# CHIP_ziffy_v5.net
KiCad netlist of a schematic drawn in EAGLE
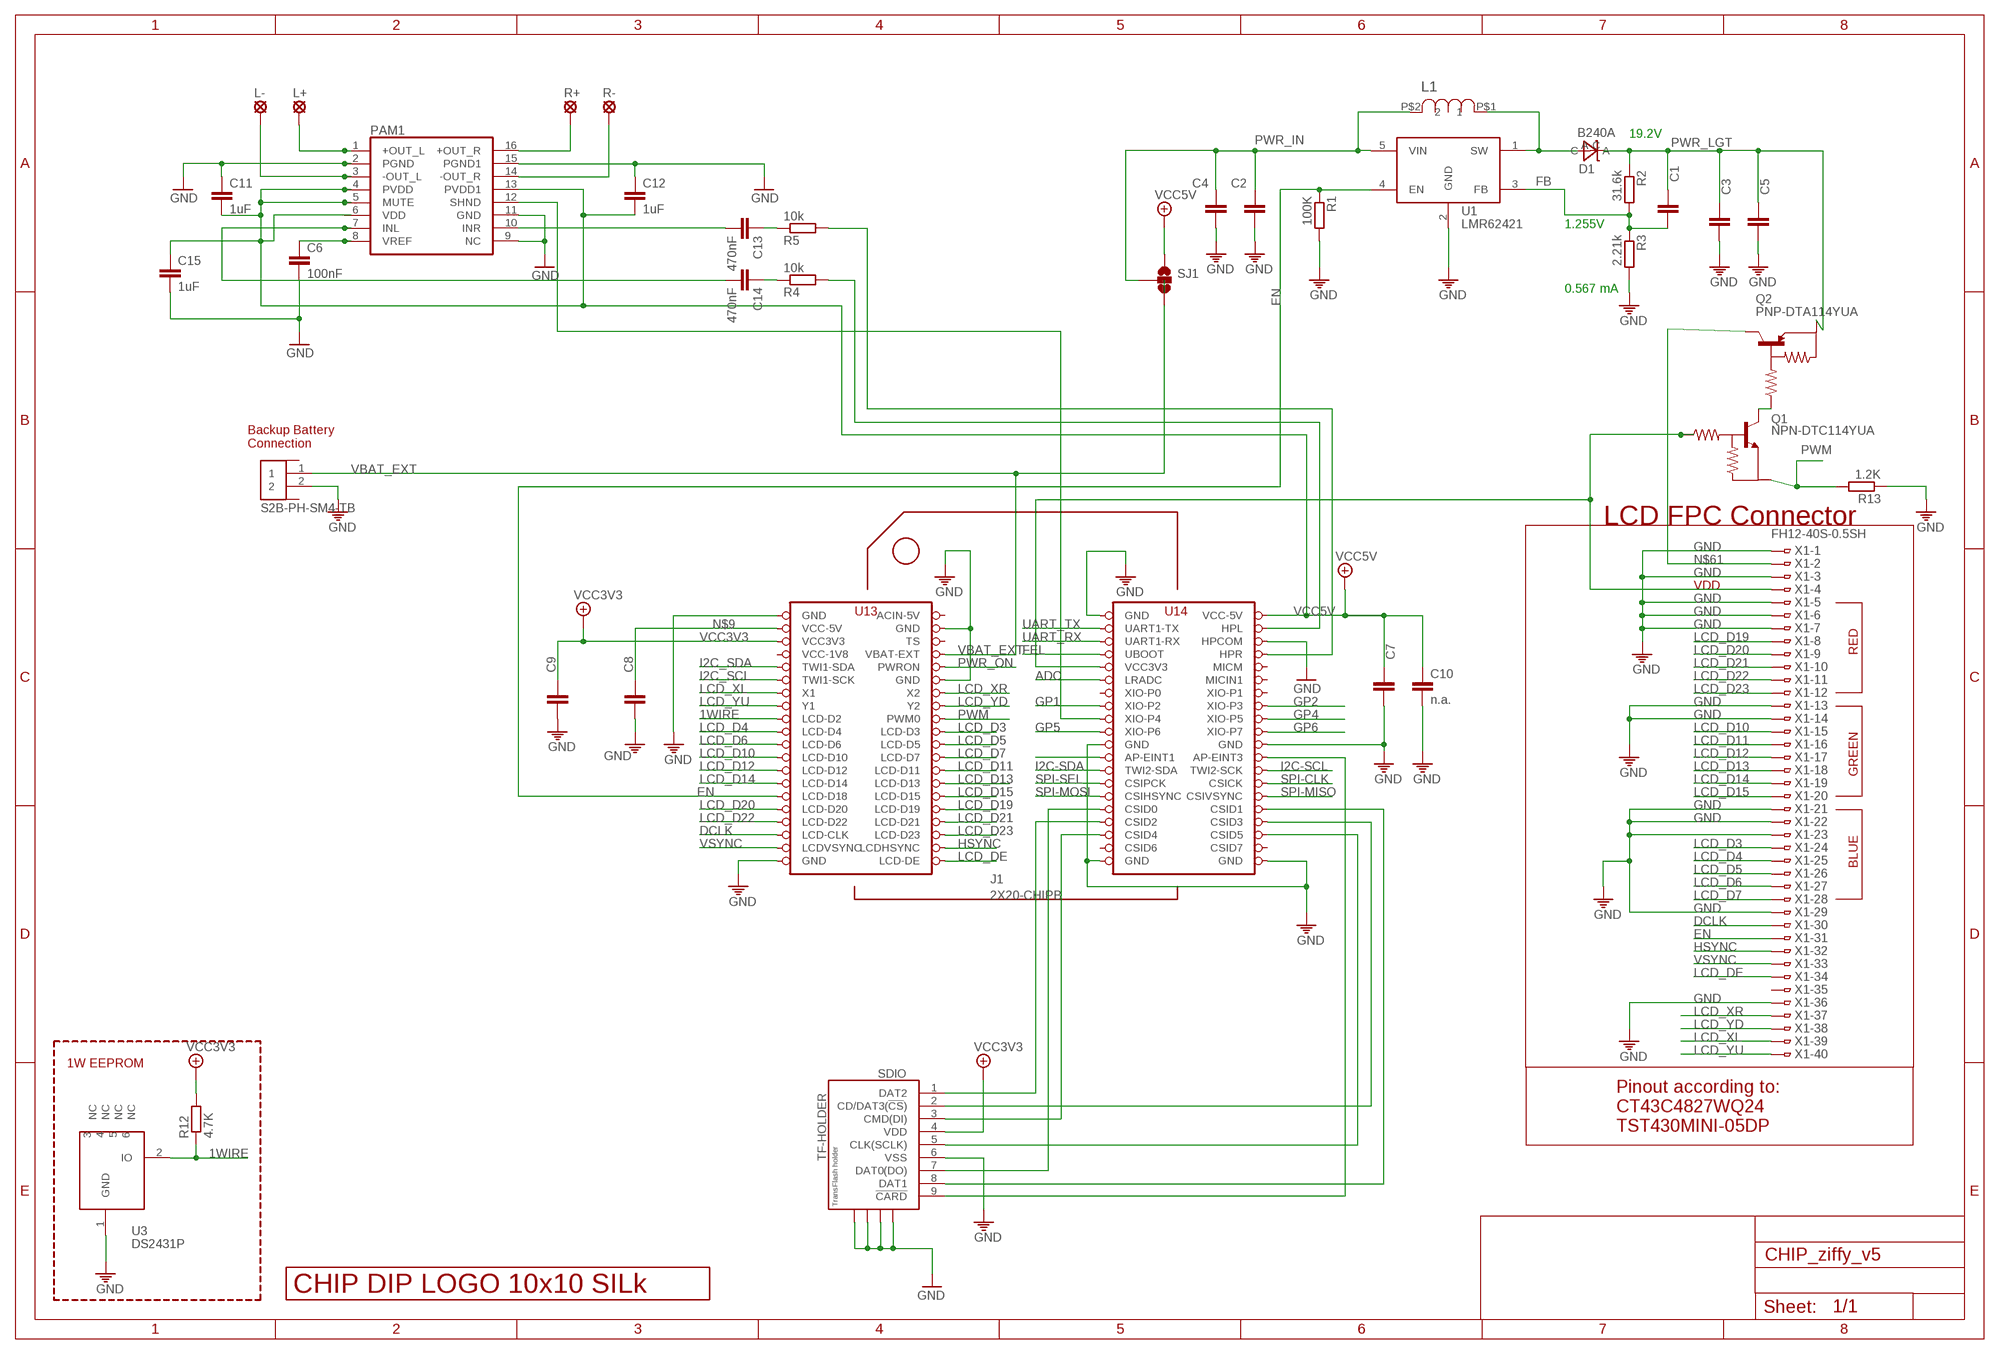
[diagram p0: schematic, sheet 1]

(export (version "E")
  (design (tool "Eeschema 10.0.6"))
  (components
    (comp (ref "C1")
      (value "220pF")
      (footprint "eagle-import:C0805")
      (libsource (lib "eagle-import") (part "C-EUC0805"))
    )
    (comp (ref "C2")
      (value "100nF")
      (footprint "eagle-import:C0805")
      (libsource (lib "eagle-import") (part "C-EUC0805"))
    )
    (comp (ref "C3")
      (value "100nF")
      (footprint "eagle-import:C0805")
      (libsource (lib "eagle-import") (part "C-EUC0805"))
    )
    (comp (ref "C4")
      (value "22uF")
      (footprint "eagle-import:C0805")
      (libsource (lib "eagle-import") (part "C-EUC0805"))
    )
    (comp (ref "C5")
      (value "22uF")
      (footprint "eagle-import:C0805")
      (libsource (lib "eagle-import") (part "C-EUC0805"))
    )
    (comp (ref "C6")
      (value "100nF")
      (footprint "eagle-import:C0805")
      (libsource (lib "eagle-import") (part "C-EUC0805"))
    )
    (comp (ref "C7")
      (value "n.a.")
      (footprint "eagle-import:C0805")
      (libsource (lib "eagle-import") (part "C-EUC0805"))
    )
    (comp (ref "C8")
      (value "100nF")
      (footprint "eagle-import:C0805")
      (libsource (lib "eagle-import") (part "C-EUC0805"))
    )
    (comp (ref "C9")
      (value "100nF")
      (footprint "eagle-import:C0805")
      (libsource (lib "eagle-import") (part "C-EUC0805"))
    )
    (comp (ref "C10")
      (value "n.a.")
      (footprint "eagle-import:C0805")
      (libsource (lib "eagle-import") (part "C-EUC0805"))
    )
    (comp (ref "C11")
      (value "1uF")
      (footprint "eagle-import:C0805")
      (libsource (lib "eagle-import") (part "C-EUC0805"))
    )
    (comp (ref "C12")
      (value "1uF")
      (footprint "eagle-import:C0805")
      (libsource (lib "eagle-import") (part "C-EUC0805"))
    )
    (comp (ref "C13")
      (value "470nF")
      (footprint "eagle-import:C0805")
      (libsource (lib "eagle-import") (part "C-EUC0805"))
    )
    (comp (ref "C14")
      (value "470nF")
      (footprint "eagle-import:C0805")
      (libsource (lib "eagle-import") (part "C-EUC0805"))
    )
    (comp (ref "C15")
      (value "1uF")
      (footprint "eagle-import:C0805")
      (libsource (lib "eagle-import") (part "C-EUC0805"))
    )
    (comp (ref "D1")
      (value "B240A")
      (footprint "eagle-import:DO-214AC")
      (fields (field (name "MFG") "DIGIKEY") (field (name "VENDOR_PART_NUMBER") "B240A-13-F"))
      (libsource (lib "eagle-import") (part "DIODE_SCHTKY_B240"))
    )
    (comp (ref "J1")
      (value "2X20-CHIPB")
      (footprint "eagle-import:2X20CHIP_SM")
      (libsource (lib "eagle-import") (part "2X20-CHIPB"))
    )
    (comp (ref "J3")
      (value "S2B-PH-SM4-TB")
      (footprint "eagle-import:S2B-PH-SM4-TB")
      (fields (field (name "MFG") "DIGIKEY") (field (name "VENDOR_PART_NUMBER") "S2B-PH-SM4-TB(LF)(SN)"))
      (libsource (lib "eagle-import") (part "S2B-PH-SM4-TB"))
    )
    (comp (ref "L+")
      (value "SE11")
      (footprint "eagle-import:SE11")
      (libsource (lib "eagle-import") (part "SE11"))
    )
    (comp (ref "L-")
      (value "SE11")
      (footprint "eagle-import:SE11")
      (libsource (lib "eagle-import") (part "SE11"))
    )
    (comp (ref "L1")
      (value "SRN6045-100M")
      (footprint "eagle-import:SRN6045")
      (fields (field (name "MFG") "DIGIKEY"))
      (libsource (lib "eagle-import") (part "SRN6045-100M"))
    )
    (comp (ref "PAM1")
      (value "PAM8403")
      (footprint "eagle-import:SOP-16")
      (libsource (lib "eagle-import") (part "PAM8403"))
    )
    (comp (ref "Q1")
      (value "NPN-DTC114YUA")
      (footprint "eagle-import:SOT323")
      (libsource (lib "eagle-import") (part "NPN-DTC114YUA"))
    )
    (comp (ref "Q2")
      (value "PNP-DTA114YUA")
      (footprint "eagle-import:SOT323")
      (libsource (lib "eagle-import") (part "PNP-DTA114YUA"))
    )
    (comp (ref "R+")
      (value "SE11")
      (footprint "eagle-import:SE11")
      (libsource (lib "eagle-import") (part "SE11"))
    )
    (comp (ref "R-")
      (value "SE11")
      (footprint "eagle-import:SE11")
      (libsource (lib "eagle-import") (part "SE11"))
    )
    (comp (ref "R1")
      (value "100K")
      (footprint "eagle-import:M0805")
      (libsource (lib "eagle-import") (part "R-EU_M0805"))
    )
    (comp (ref "R2")
      (value "31.6k")
      (footprint "eagle-import:M0805")
      (libsource (lib "eagle-import") (part "R-EU_M0805"))
    )
    (comp (ref "R3")
      (value "2.21k")
      (footprint "eagle-import:M0805")
      (libsource (lib "eagle-import") (part "R-EU_M0805"))
    )
    (comp (ref "R4")
      (value "10k")
      (footprint "eagle-import:R0805")
      (libsource (lib "eagle-import") (part "R-EU_R0805"))
    )
    (comp (ref "R5")
      (value "10k")
      (footprint "eagle-import:R0805")
      (libsource (lib "eagle-import") (part "R-EU_R0805"))
    )
    (comp (ref "R12")
      (value "4.7K")
      (footprint "eagle-import:M0805")
      (libsource (lib "eagle-import") (part "R-EU_M0805"))
    )
    (comp (ref "R13")
      (value "1.2K")
      (footprint "eagle-import:M0805")
      (libsource (lib "eagle-import") (part "R-EU_M0805"))
    )
    (comp (ref "SDIO")
      (value "TF-HOLDER")
      (footprint "eagle-import:TF-PULL")
      (libsource (lib "eagle-import") (part "TF-HOLDER"))
    )
    (comp (ref "SJ1")
      (value "SOLDERJUMPER_2WAYT")
      (footprint "eagle-import:SJ_2")
      (libsource (lib "eagle-import") (part "SOLDERJUMPER_2WAYT"))
    )
    (comp (ref "U$2")
      (value "LOGO_10X10_SILK")
      (footprint "eagle-import:LOGO2_10X10_SILK")
      (libsource (lib "eagle-import") (part "LOGO_10X10_SILK"))
    )
    (comp (ref "U1")
      (value "LMR62421")
      (footprint "eagle-import:SOT23-5")
      (fields (field (name "MFG") "DIGIKEY") (field (name "VENDOR_PART_NUMBER") "LMR62421XMFE/NOPB"))
      (libsource (lib "eagle-import") (part "LMR62421"))
    )
    (comp (ref "U3")
      (value "DS2431P")
      (footprint "eagle-import:TSOC6")
      (fields (field (name "MFG") "DIGIKEY") (field (name "VENDOR_PART_NUMBER") "DS2431P+T&R"))
      (libsource (lib "eagle-import") (part "DS2431P"))
    )
    (comp (ref "X1")
      (value "FH12-40S-0.5SH")
      (footprint "eagle-import:FH12-40S-0.5SH")
      (fields (field (name "MFG") "DIGIKEY") (field (name "VENDOR_PART_NUMBER") "FH12-40S-0.5SH(55)"))
      (libsource (lib "eagle-import") (part "FH12-40S-0.5SH"))
    )
  )
  (nets
    (net (code "1") (name "/1WIRE") (class "Default")
      (node (ref "J1") (pin "LCD-D2") (pinfunction "LCD-D2_LCD-D2") (pintype "passive"))
      (node (ref "R12") (pin "1") (pinfunction "1_1") (pintype "passive"))
      (node (ref "U3") (pin "2") (pinfunction "IO_2") (pintype "bidirectional"))
    )
    (net (code "2") (name "/ADC") (class "Default")
      (node (ref "J1") (pin "LRADC") (pinfunction "LRADC_LRADC") (pintype "passive"))
    )
    (net (code "3") (name "/DCLK") (class "Default")
      (node (ref "J1") (pin "LCD-CLK") (pinfunction "LCD-CLK_LCD-CLK") (pintype "passive"))
      (node (ref "X1") (pin "30") (pinfunction "1_30") (pintype "passive"))
    )
    (net (code "4") (name "/EN") (class "Default")
      (node (ref "J1") (pin "LCD-D18") (pinfunction "LCD-D18_LCD-D18") (pintype "passive"))
      (node (ref "R1") (pin "1") (pinfunction "1_1") (pintype "passive"))
      (node (ref "U1") (pin "4") (pinfunction "EN_4") (pintype "bidirectional"))
      (node (ref "X1") (pin "31") (pinfunction "1_31") (pintype "passive"))
    )
    (net (code "5") (name "/FB") (class "Default")
      (node (ref "C1") (pin "2") (pinfunction "2_2") (pintype "passive"))
      (node (ref "R2") (pin "2") (pinfunction "2_2") (pintype "passive"))
      (node (ref "R3") (pin "1") (pinfunction "1_1") (pintype "passive"))
      (node (ref "U1") (pin "3") (pinfunction "FB_3") (pintype "bidirectional"))
    )
    (net (code "6") (name "/FEL") (class "Default")
      (node (ref "J1") (pin "FEL") (pinfunction "UBOOT_FEL") (pintype "passive"))
    )
    (net (code "7") (name "/GP1") (class "Default")
      (node (ref "J1") (pin "XIO-P2") (pinfunction "XIO-P2_XIO-P2") (pintype "passive"))
    )
    (net (code "8") (name "/GP2") (class "Default")
      (node (ref "J1") (pin "XIO-P3") (pinfunction "XIO-P3_XIO-P3") (pintype "passive"))
    )
    (net (code "9") (name "/GP4") (class "Default")
      (node (ref "J1") (pin "XIO-P5") (pinfunction "XIO-P5_XIO-P5") (pintype "passive"))
    )
    (net (code "10") (name "/GP5") (class "Default")
      (node (ref "J1") (pin "XIO-P6") (pinfunction "XIO-P6_XIO-P6") (pintype "passive"))
    )
    (net (code "11") (name "/GP6") (class "Default")
      (node (ref "J1") (pin "XIO-P7") (pinfunction "XIO-P7_XIO-P7") (pintype "passive"))
    )
    (net (code "12") (name "/HSYNC") (class "Default")
      (node (ref "J1") (pin "LCD-HSYNC") (pinfunction "LCDHSYNC_LCD-HSYNC") (pintype "passive"))
      (node (ref "X1") (pin "32") (pinfunction "1_32") (pintype "passive"))
    )
    (net (code "13") (name "/I2C-SCL") (class "Default")
      (node (ref "J1") (pin "TWI2-SCK") (pinfunction "TWI2-SCK_TWI2-SCK") (pintype "passive"))
    )
    (net (code "14") (name "/I2C-SDA") (class "Default")
      (node (ref "J1") (pin "TWI2-SDA") (pinfunction "TWI2-SDA_TWI2-SDA") (pintype "passive"))
    )
    (net (code "15") (name "/I2C_SCL") (class "Default")
      (node (ref "J1") (pin "TWI1-SCK") (pinfunction "TWI1-SCK_TWI1-SCK") (pintype "passive"))
    )
    (net (code "16") (name "/I2C_SDA") (class "Default")
      (node (ref "J1") (pin "TWI1-SDA") (pinfunction "TWI1-SDA_TWI1-SDA") (pintype "passive"))
    )
    (net (code "17") (name "/LCD_D3") (class "Default")
      (node (ref "J1") (pin "LCD-D3") (pinfunction "LCD-D3_LCD-D3") (pintype "passive"))
      (node (ref "X1") (pin "24") (pinfunction "1_24") (pintype "passive"))
    )
    (net (code "18") (name "/LCD_D4") (class "Default")
      (node (ref "J1") (pin "LCD-D4") (pinfunction "LCD-D4_LCD-D4") (pintype "passive"))
      (node (ref "X1") (pin "25") (pinfunction "1_25") (pintype "passive"))
    )
    (net (code "19") (name "/LCD_D5") (class "Default")
      (node (ref "J1") (pin "LCD-D5") (pinfunction "LCD-D5_LCD-D5") (pintype "passive"))
      (node (ref "X1") (pin "26") (pinfunction "1_26") (pintype "passive"))
    )
    (net (code "20") (name "/LCD_D6") (class "Default")
      (node (ref "J1") (pin "LCD-D6") (pinfunction "LCD-D6_LCD-D6") (pintype "passive"))
      (node (ref "X1") (pin "27") (pinfunction "1_27") (pintype "passive"))
    )
    (net (code "21") (name "/LCD_D7") (class "Default")
      (node (ref "J1") (pin "LCD-D7") (pinfunction "LCD-D7_LCD-D7") (pintype "passive"))
      (node (ref "X1") (pin "28") (pinfunction "1_28") (pintype "passive"))
    )
    (net (code "22") (name "/LCD_D10") (class "Default")
      (node (ref "J1") (pin "LCD-D10") (pinfunction "LCD-D10_LCD-D10") (pintype "passive"))
      (node (ref "X1") (pin "15") (pinfunction "1_15") (pintype "passive"))
    )
    (net (code "23") (name "/LCD_D11") (class "Default")
      (node (ref "J1") (pin "LCD-D11") (pinfunction "LCD-D11_LCD-D11") (pintype "passive"))
      (node (ref "X1") (pin "16") (pinfunction "1_16") (pintype "passive"))
    )
    (net (code "24") (name "/LCD_D12") (class "Default")
      (node (ref "J1") (pin "LCD-D12") (pinfunction "LCD-D12_LCD-D12") (pintype "passive"))
      (node (ref "X1") (pin "17") (pinfunction "1_17") (pintype "passive"))
    )
    (net (code "25") (name "/LCD_D13") (class "Default")
      (node (ref "J1") (pin "LCD-D13") (pinfunction "LCD-D13_LCD-D13") (pintype "passive"))
      (node (ref "X1") (pin "18") (pinfunction "1_18") (pintype "passive"))
    )
    (net (code "26") (name "/LCD_D14") (class "Default")
      (node (ref "J1") (pin "LCD-D14") (pinfunction "LCD-D14_LCD-D14") (pintype "passive"))
      (node (ref "X1") (pin "19") (pinfunction "1_19") (pintype "passive"))
    )
    (net (code "27") (name "/LCD_D15") (class "Default")
      (node (ref "J1") (pin "LCD-D15") (pinfunction "LCD-D15_LCD-D15") (pintype "passive"))
      (node (ref "X1") (pin "20") (pinfunction "1_20") (pintype "passive"))
    )
    (net (code "28") (name "/LCD_D19") (class "Default")
      (node (ref "J1") (pin "LCD-D19") (pinfunction "LCD-D19_LCD-D19") (pintype "passive"))
      (node (ref "X1") (pin "8") (pinfunction "1_8") (pintype "passive"))
    )
    (net (code "29") (name "/LCD_D20") (class "Default")
      (node (ref "J1") (pin "LCD-D20") (pinfunction "LCD-D20_LCD-D20") (pintype "passive"))
      (node (ref "X1") (pin "9") (pinfunction "1_9") (pintype "passive"))
    )
    (net (code "30") (name "/LCD_D21") (class "Default")
      (node (ref "J1") (pin "LCD-D21") (pinfunction "LCD-D21_LCD-D21") (pintype "passive"))
      (node (ref "X1") (pin "10") (pinfunction "1_10") (pintype "passive"))
    )
    (net (code "31") (name "/LCD_D22") (class "Default")
      (node (ref "J1") (pin "LCD-D22") (pinfunction "LCD-D22_LCD-D22") (pintype "passive"))
      (node (ref "X1") (pin "11") (pinfunction "1_11") (pintype "passive"))
    )
    (net (code "32") (name "/LCD_D23") (class "Default")
      (node (ref "J1") (pin "LCD-D23") (pinfunction "LCD-D23_LCD-D23") (pintype "passive"))
      (node (ref "X1") (pin "12") (pinfunction "1_12") (pintype "passive"))
    )
    (net (code "33") (name "/LCD_DE") (class "Default")
      (node (ref "J1") (pin "LCD-DE") (pinfunction "LCD-DE_LCD-DE") (pintype "passive"))
      (node (ref "X1") (pin "34") (pinfunction "1_34") (pintype "passive"))
    )
    (net (code "34") (name "/LCD_XL") (class "Default")
      (node (ref "J1") (pin "X1") (pinfunction "X1_X1") (pintype "passive"))
      (node (ref "X1") (pin "39") (pinfunction "1_39") (pintype "passive"))
    )
    (net (code "35") (name "/LCD_XR") (class "Default")
      (node (ref "J1") (pin "X2") (pinfunction "X2_X2") (pintype "passive"))
      (node (ref "X1") (pin "37") (pinfunction "1_37") (pintype "passive"))
    )
    (net (code "36") (name "/LCD_YD") (class "Default")
      (node (ref "J1") (pin "Y2") (pinfunction "Y2_Y2") (pintype "passive"))
      (node (ref "X1") (pin "38") (pinfunction "1_38") (pintype "passive"))
    )
    (net (code "37") (name "/LCD_YU") (class "Default")
      (node (ref "J1") (pin "Y1") (pinfunction "Y1_Y1") (pintype "passive"))
      (node (ref "X1") (pin "40") (pinfunction "1_40") (pintype "passive"))
    )
    (net (code "38") (name "/N$9") (class "Default")
      (node (ref "C8") (pin "1") (pinfunction "1_1") (pintype "passive"))
      (node (ref "J1") (pin "VCC5V@0") (pinfunction "VCC-5V_VCC5V@0") (pintype "power_in"))
    )
    (net (code "39") (name "/N$61") (class "Default")
      (node (ref "Q2") (pin "3") (pinfunction "OUT_3") (pintype "passive"))
      (node (ref "X1") (pin "2") (pinfunction "1_2") (pintype "passive"))
    )
    (net (code "40") (name "/PWM") (class "Default")
      (node (ref "J1") (pin "PWM0") (pinfunction "PWM0_PWM0") (pintype "passive"))
      (node (ref "Q1") (pin "2") (pinfunction "GND_2") (pintype "passive"))
      (node (ref "R13") (pin "2") (pinfunction "2_2") (pintype "passive"))
    )
    (net (code "41") (name "/PWR_IN") (class "Default")
      (node (ref "C2") (pin "1") (pinfunction "1_1") (pintype "passive"))
      (node (ref "C4") (pin "1") (pinfunction "1_1") (pintype "passive"))
      (node (ref "L1") (pin "P$2") (pinfunction "2_P$2") (pintype "passive"))
      (node (ref "SJ1") (pin "2") (pinfunction "2_2") (pintype "passive"))
      (node (ref "U1") (pin "5") (pinfunction "VIN_5") (pintype "bidirectional"))
    )
    (net (code "42") (name "/PWR_LGT") (class "Default")
      (node (ref "C1") (pin "1") (pinfunction "1_1") (pintype "passive"))
      (node (ref "C3") (pin "1") (pinfunction "1_1") (pintype "passive"))
      (node (ref "C5") (pin "1") (pinfunction "1_1") (pintype "passive"))
      (node (ref "D1") (pin "C") (pinfunction "C_C") (pintype "bidirectional"))
      (node (ref "Q2") (pin "2") (pinfunction "GND_2") (pintype "passive"))
      (node (ref "R2") (pin "1") (pinfunction "1_1") (pintype "passive"))
    )
    (net (code "43") (name "/PWR_ON") (class "Default")
      (node (ref "J1") (pin "PWRON") (pinfunction "PWRON_PWRON") (pintype "passive"))
    )
    (net (code "44") (name "/SPI-CLK") (class "Default")
      (node (ref "J1") (pin "CSICK") (pinfunction "CSICK_CSICK") (pintype "passive"))
    )
    (net (code "45") (name "/SPI-MISO") (class "Default")
      (node (ref "J1") (pin "CSIVSYNC") (pinfunction "CSIVSYNC_CSIVSYNC") (pintype "passive"))
    )
    (net (code "46") (name "/SPI-MOSI") (class "Default")
      (node (ref "J1") (pin "CSIHSYNC") (pinfunction "CSIHSYNC_CSIHSYNC") (pintype "passive"))
    )
    (net (code "47") (name "/SPI-SEL") (class "Default")
      (node (ref "J1") (pin "CSIPCK") (pinfunction "CSIPCK_CSIPCK") (pintype "passive"))
    )
    (net (code "48") (name "/UART_RX") (class "Default")
      (node (ref "J1") (pin "UART1-RX") (pinfunction "UART1-RX_UART1-RX") (pintype "passive"))
    )
    (net (code "49") (name "/UART_TX") (class "Default")
      (node (ref "J1") (pin "UART1-TX") (pinfunction "UART1-TX_UART1-TX") (pintype "passive"))
    )
    (net (code "50") (name "/VBAT_EXT") (class "Default")
      (node (ref "J1") (pin "BAT") (pinfunction "VBAT-EXT_BAT") (pintype "passive"))
      (node (ref "J3") (pin "1") (pinfunction "1_1") (pintype "bidirectional"))
      (node (ref "SJ1") (pin "3") (pinfunction "3_3") (pintype "passive"))
    )
    (net (code "51") (name "/VCC-1V8") (class "Default")
      (node (ref "J1") (pin "VCC1V8") (pinfunction "VCC-1V8_VCC1V8") (pintype "power_in"))
    )
    (net (code "52") (name "/VSYNC") (class "Default")
      (node (ref "J1") (pin "LCD-VSYNC") (pinfunction "LCDVSYNC_LCD-VSYNC") (pintype "passive"))
      (node (ref "X1") (pin "33") (pinfunction "1_33") (pintype "passive"))
    )
    (net (code "53") (name "GND") (class "Default")
      (node (ref "C10") (pin "2") (pinfunction "2_2") (pintype "passive"))
      (node (ref "C11") (pin "1") (pinfunction "1_1") (pintype "passive"))
      (node (ref "C12") (pin "1") (pinfunction "1_1") (pintype "passive"))
      (node (ref "C15") (pin "2") (pinfunction "2_2") (pintype "passive"))
      (node (ref "C2") (pin "2") (pinfunction "2_2") (pintype "passive"))
      (node (ref "C3") (pin "2") (pinfunction "2_2") (pintype "passive"))
      (node (ref "C4") (pin "2") (pinfunction "2_2") (pintype "passive"))
      (node (ref "C5") (pin "2") (pinfunction "2_2") (pintype "passive"))
      (node (ref "C6") (pin "2") (pinfunction "2_2") (pintype "passive"))
      (node (ref "C7") (pin "2") (pinfunction "2_2") (pintype "passive"))
      (node (ref "C8") (pin "2") (pinfunction "2_2") (pintype "passive"))
      (node (ref "C9") (pin "2") (pinfunction "2_2") (pintype "passive"))
      (node (ref "J1") (pin "GND@1") (pinfunction "GND_GND@1") (pintype "power_in"))
      (node (ref "J1") (pin "GND@10") (pinfunction "GND_GND@10") (pintype "power_in"))
      (node (ref "J1") (pin "GND@2") (pinfunction "GND_GND@2") (pintype "power_in"))
      (node (ref "J1") (pin "GND@3") (pinfunction "GND_GND@3") (pintype "power_in"))
      (node (ref "J1") (pin "GND@4") (pinfunction "GND_GND@4") (pintype "power_in"))
      (node (ref "J1") (pin "GND@5") (pinfunction "GND_GND@5") (pintype "power_in"))
      (node (ref "J1") (pin "GND@6") (pinfunction "GND_GND@6") (pintype "power_in"))
      (node (ref "J1") (pin "GND@7") (pinfunction "GND_GND@7") (pintype "power_in"))
      (node (ref "J1") (pin "GND@8") (pinfunction "GND_GND@8") (pintype "power_in"))
      (node (ref "J1") (pin "HPCOM") (pinfunction "HPCOM_HPCOM") (pintype "passive"))
      (node (ref "J3") (pin "2") (pinfunction "2_2") (pintype "bidirectional"))
      (node (ref "PAM1") (pin "11") (pinfunction "GND_11") (pintype "output"))
      (node (ref "PAM1") (pin "15") (pinfunction "PGND1_15") (pintype "output"))
      (node (ref "PAM1") (pin "2") (pinfunction "PGND_2") (pintype "input"))
      (node (ref "PAM1") (pin "9") (pinfunction "NC_9") (pintype "output"))
      (node (ref "R1") (pin "2") (pinfunction "2_2") (pintype "passive"))
      (node (ref "R13") (pin "1") (pinfunction "1_1") (pintype "passive"))
      (node (ref "R3") (pin "2") (pinfunction "2_2") (pintype "passive"))
      (node (ref "SDIO") (pin "6") (pinfunction "VSS_6") (pintype "power_in"))
      (node (ref "SDIO") (pin "S1") (pinfunction "S1_S1") (pintype "passive"))
      (node (ref "SDIO") (pin "S2") (pinfunction "S2_S2") (pintype "passive"))
      (node (ref "SDIO") (pin "S3") (pinfunction "S3_S3") (pintype "passive"))
      (node (ref "SDIO") (pin "S4") (pinfunction "S4_S4") (pintype "passive"))
      (node (ref "U1") (pin "2") (pinfunction "GND_2") (pintype "bidirectional"))
      (node (ref "U3") (pin "1") (pinfunction "GND_1") (pintype "bidirectional"))
      (node (ref "X1") (pin "1") (pinfunction "1_1") (pintype "passive"))
      (node (ref "X1") (pin "13") (pinfunction "1_13") (pintype "passive"))
      (node (ref "X1") (pin "14") (pinfunction "1_14") (pintype "passive"))
      (node (ref "X1") (pin "21") (pinfunction "1_21") (pintype "passive"))
      (node (ref "X1") (pin "22") (pinfunction "1_22") (pintype "passive"))
      (node (ref "X1") (pin "23") (pinfunction "1_23") (pintype "passive"))
      (node (ref "X1") (pin "29") (pinfunction "1_29") (pintype "passive"))
      (node (ref "X1") (pin "3") (pinfunction "1_3") (pintype "passive"))
      (node (ref "X1") (pin "36") (pinfunction "1_36") (pintype "passive"))
      (node (ref "X1") (pin "5") (pinfunction "1_5") (pintype "passive"))
      (node (ref "X1") (pin "6") (pinfunction "1_6") (pintype "passive"))
      (node (ref "X1") (pin "7") (pinfunction "1_7") (pintype "passive"))
    )
    (net (code "54") (name "Net-(C13-Pad1)") (class "Default")
      (node (ref "C13") (pin "1") (pinfunction "1_1") (pintype "passive"))
      (node (ref "R5") (pin "1") (pinfunction "1_1") (pintype "passive"))
    )
    (net (code "55") (name "Net-(C14-Pad1)") (class "Default")
      (node (ref "C14") (pin "1") (pinfunction "1_1") (pintype "passive"))
      (node (ref "R4") (pin "1") (pinfunction "1_1") (pintype "passive"))
    )
    (net (code "56") (name "Net-(J1-PadHPL)") (class "Default")
      (node (ref "J1") (pin "HPL") (pinfunction "HPL_HPL") (pintype "passive"))
      (node (ref "R4") (pin "2") (pinfunction "2_2") (pintype "passive"))
    )
    (net (code "57") (name "Net-(J1-PadHPR)") (class "Default")
      (node (ref "J1") (pin "HPR") (pinfunction "HPR_HPR") (pintype "passive"))
      (node (ref "R5") (pin "2") (pinfunction "2_2") (pintype "passive"))
    )
    (net (code "58") (name "Net-(L1-1)") (class "Default")
      (node (ref "D1") (pin "A") (pinfunction "A_A") (pintype "bidirectional"))
      (node (ref "L1") (pin "P$1") (pinfunction "1_P$1") (pintype "passive"))
      (node (ref "U1") (pin "1") (pinfunction "SW_1") (pintype "bidirectional"))
    )
    (net (code "59") (name "Net-(PAM1-+OUT_L)") (class "Default")
      (node (ref "L+") (pin "MP") (pinfunction "MP_MP") (pintype "passive"))
      (node (ref "PAM1") (pin "1") (pinfunction "+OUT_L_1") (pintype "input"))
    )
    (net (code "60") (name "Net-(PAM1-+OUT_R)") (class "Default")
      (node (ref "PAM1") (pin "16") (pinfunction "+OUT_R_16") (pintype "output"))
      (node (ref "R+") (pin "MP") (pinfunction "MP_MP") (pintype "passive"))
    )
    (net (code "61") (name "Net-(PAM1--OUT_L)") (class "Default")
      (node (ref "L-") (pin "MP") (pinfunction "MP_MP") (pintype "passive"))
      (node (ref "PAM1") (pin "3") (pinfunction "-OUT_L_3") (pintype "input"))
    )
    (net (code "62") (name "Net-(PAM1--OUT_R)") (class "Default")
      (node (ref "PAM1") (pin "14") (pinfunction "-OUT_R_14") (pintype "output"))
      (node (ref "R-") (pin "MP") (pinfunction "MP_MP") (pintype "passive"))
    )
    (net (code "63") (name "Net-(PAM1-INL)") (class "Default")
      (node (ref "C14") (pin "2") (pinfunction "2_2") (pintype "passive"))
      (node (ref "PAM1") (pin "7") (pinfunction "INL_7") (pintype "input"))
    )
    (net (code "64") (name "Net-(PAM1-INR)") (class "Default")
      (node (ref "C13") (pin "2") (pinfunction "2_2") (pintype "passive"))
      (node (ref "PAM1") (pin "10") (pinfunction "INR_10") (pintype "output"))
    )
    (net (code "65") (name "Net-(PAM1-SHND)") (class "Default")
      (node (ref "J1") (pin "XIO-P4") (pinfunction "XIO-P4_XIO-P4") (pintype "passive"))
      (node (ref "PAM1") (pin "12") (pinfunction "SHND_12") (pintype "output"))
    )
    (net (code "66") (name "Net-(PAM1-VREF)") (class "Default")
      (node (ref "C6") (pin "1") (pinfunction "1_1") (pintype "passive"))
      (node (ref "PAM1") (pin "8") (pinfunction "VREF_8") (pintype "input"))
    )
    (net (code "67") (name "Net-(Q1-IN)") (class "Default")
      (node (ref "J1") (pin "VCC3V3@1") (pinfunction "VCC3V3_VCC3V3@1") (pintype "power_in"))
      (node (ref "Q1") (pin "1") (pinfunction "IN_1") (pintype "passive"))
      (node (ref "X1") (pin "4") (pinfunction "1_4") (pintype "passive"))
    )
    (net (code "68") (name "Net-(Q1-OUT)") (class "Default")
      (node (ref "Q1") (pin "3") (pinfunction "OUT_3") (pintype "passive"))
      (node (ref "Q2") (pin "1") (pinfunction "IN_1") (pintype "passive"))
    )
    (net (code "69") (name "Net-(SDIO-CD{slash}DAT3(~{CS}))") (class "Default")
      (node (ref "J1") (pin "CSID3") (pinfunction "CSID3_CSID3") (pintype "passive"))
      (node (ref "SDIO") (pin "2") (pinfunction "CD/DAT3(~{CS})_2") (pintype "bidirectional"))
    )
    (net (code "70") (name "Net-(SDIO-CLK(SCLK))") (class "Default")
      (node (ref "J1") (pin "CSID5") (pinfunction "CSID5_CSID5") (pintype "passive"))
      (node (ref "SDIO") (pin "5") (pinfunction "CLK(SCLK)_5") (pintype "input"))
    )
    (net (code "71") (name "Net-(SDIO-CMD(DI))") (class "Default")
      (node (ref "J1") (pin "CSID4") (pinfunction "CSID4_CSID4") (pintype "passive"))
      (node (ref "SDIO") (pin "3") (pinfunction "CMD(DI)_3") (pintype "bidirectional"))
    )
    (net (code "72") (name "Net-(SDIO-DAT0(DO))") (class "Default")
      (node (ref "J1") (pin "CSID0") (pinfunction "CSID0_CSID0") (pintype "passive"))
      (node (ref "SDIO") (pin "7") (pinfunction "DAT0(DO)_7") (pintype "bidirectional"))
    )
    (net (code "73") (name "Net-(SDIO-DAT1)") (class "Default")
      (node (ref "J1") (pin "CSID1") (pinfunction "CSID1_CSID1") (pintype "passive"))
      (node (ref "SDIO") (pin "8") (pinfunction "DAT1_8") (pintype "bidirectional"))
    )
    (net (code "74") (name "Net-(SDIO-DAT2)") (class "Default")
      (node (ref "J1") (pin "CSID2") (pinfunction "CSID2_CSID2") (pintype "passive"))
      (node (ref "SDIO") (pin "1") (pinfunction "DAT2_1") (pintype "bidirectional"))
    )
    (net (code "75") (name "Net-(SDIO-~{CARD})") (class "Default")
      (node (ref "J1") (pin "AP-EINT3") (pinfunction "AP-EINT3_AP-EINT3") (pintype "passive"))
      (node (ref "SDIO") (pin "9") (pinfunction "~{CARD}_9") (pintype "passive"))
    )
    (net (code "76") (name "VCC3V3") (class "Default")
      (node (ref "C9") (pin "1") (pinfunction "1_1") (pintype "passive"))
      (node (ref "J1") (pin "VCC3V3") (pinfunction "VCC3V3_VCC3V3") (pintype "power_in"))
      (node (ref "R12") (pin "2") (pinfunction "2_2") (pintype "passive"))
      (node (ref "SDIO") (pin "4") (pinfunction "VDD_4") (pintype "power_in"))
    )
    (net (code "77") (name "VCC5V") (class "Default")
      (node (ref "C10") (pin "1") (pinfunction "1_1") (pintype "passive"))
      (node (ref "C11") (pin "2") (pinfunction "2_2") (pintype "passive"))
      (node (ref "C12") (pin "2") (pinfunction "2_2") (pintype "passive"))
      (node (ref "C15") (pin "1") (pinfunction "1_1") (pintype "passive"))
      (node (ref "C7") (pin "1") (pinfunction "1_1") (pintype "passive"))
      (node (ref "J1") (pin "VCC5V@1") (pinfunction "VCC-5V_VCC5V@1") (pintype "power_in"))
      (node (ref "PAM1") (pin "13") (pinfunction "PVDD1_13") (pintype "output"))
      (node (ref "PAM1") (pin "4") (pinfunction "PVDD_4") (pintype "input"))
      (node (ref "PAM1") (pin "5") (pinfunction "MUTE_5") (pintype "input"))
      (node (ref "PAM1") (pin "6") (pinfunction "VDD_6") (pintype "input"))
      (node (ref "SJ1") (pin "1") (pinfunction "1_1") (pintype "passive"))
    )
    (net (code "78") (name "unconnected-(J1-ACIN-5V-PadCHG-IN)") (class "Default")
      (node (ref "J1") (pin "CHG-IN") (pinfunction "ACIN-5V_CHG-IN") (pintype "passive"))
    )
    (net (code "79") (name "unconnected-(J1-PadAP-EINT1)") (class "Default")
      (node (ref "J1") (pin "AP-EINT1") (pinfunction "AP-EINT1_AP-EINT1") (pintype "passive"))
    )
    (net (code "80") (name "unconnected-(J1-PadCSID6)") (class "Default")
      (node (ref "J1") (pin "CSID6") (pinfunction "CSID6_CSID6") (pintype "passive"))
    )
    (net (code "81") (name "unconnected-(J1-PadCSID7)") (class "Default")
      (node (ref "J1") (pin "CSID7") (pinfunction "CSID7_CSID7") (pintype "passive"))
    )
    (net (code "82") (name "unconnected-(J1-PadMICIN1)") (class "Default")
      (node (ref "J1") (pin "MICIN1") (pinfunction "MICIN1_MICIN1") (pintype "passive"))
    )
    (net (code "83") (name "unconnected-(J1-PadMICM)") (class "Default")
      (node (ref "J1") (pin "MICM") (pinfunction "MICM_MICM") (pintype "passive"))
    )
    (net (code "84") (name "unconnected-(J1-PadTS)") (class "Default")
      (node (ref "J1") (pin "TS") (pinfunction "TS_TS") (pintype "passive"))
    )
    (net (code "85") (name "unconnected-(J1-PadXIO-P0)") (class "Default")
      (node (ref "J1") (pin "XIO-P0") (pinfunction "XIO-P0_XIO-P0") (pintype "passive"))
    )
    (net (code "86") (name "unconnected-(J1-PadXIO-P1)") (class "Default")
      (node (ref "J1") (pin "XIO-P1") (pinfunction "XIO-P1_XIO-P1") (pintype "passive"))
    )
    (net (code "87") (name "unconnected-(J3-PadMNT1)") (class "Default")
      (node (ref "J3") (pin "MNT1") (pinfunction "MNT1_MNT1") (pintype "no_connect"))
    )
    (net (code "88") (name "unconnected-(J3-PadMNT2)") (class "Default")
      (node (ref "J3") (pin "MNT2") (pinfunction "MNT2_MNT2") (pintype "no_connect"))
    )
    (net (code "89") (name "unconnected-(U3-NC-Pad3)") (class "Default")
      (node (ref "U3") (pin "3") (pinfunction "NC_3") (pintype "bidirectional"))
    )
    (net (code "90") (name "unconnected-(U3-NC-Pad4)") (class "Default")
      (node (ref "U3") (pin "4") (pinfunction "NC_4") (pintype "bidirectional"))
    )
    (net (code "91") (name "unconnected-(U3-NC-Pad5)") (class "Default")
      (node (ref "U3") (pin "5") (pinfunction "NC_5") (pintype "bidirectional"))
    )
    (net (code "92") (name "unconnected-(U3-NC-Pad6)") (class "Default")
      (node (ref "U3") (pin "6") (pinfunction "NC_6") (pintype "bidirectional"))
    )
    (net (code "93") (name "unconnected-(X1AC-1-Pad35)") (class "Default")
      (node (ref "X1") (pin "35") (pinfunction "1_35") (pintype "passive"))
    )
  )
)
